# BuckRegulatorOnSer.net
KiCad netlist of a schematic drawn in Altium Designer
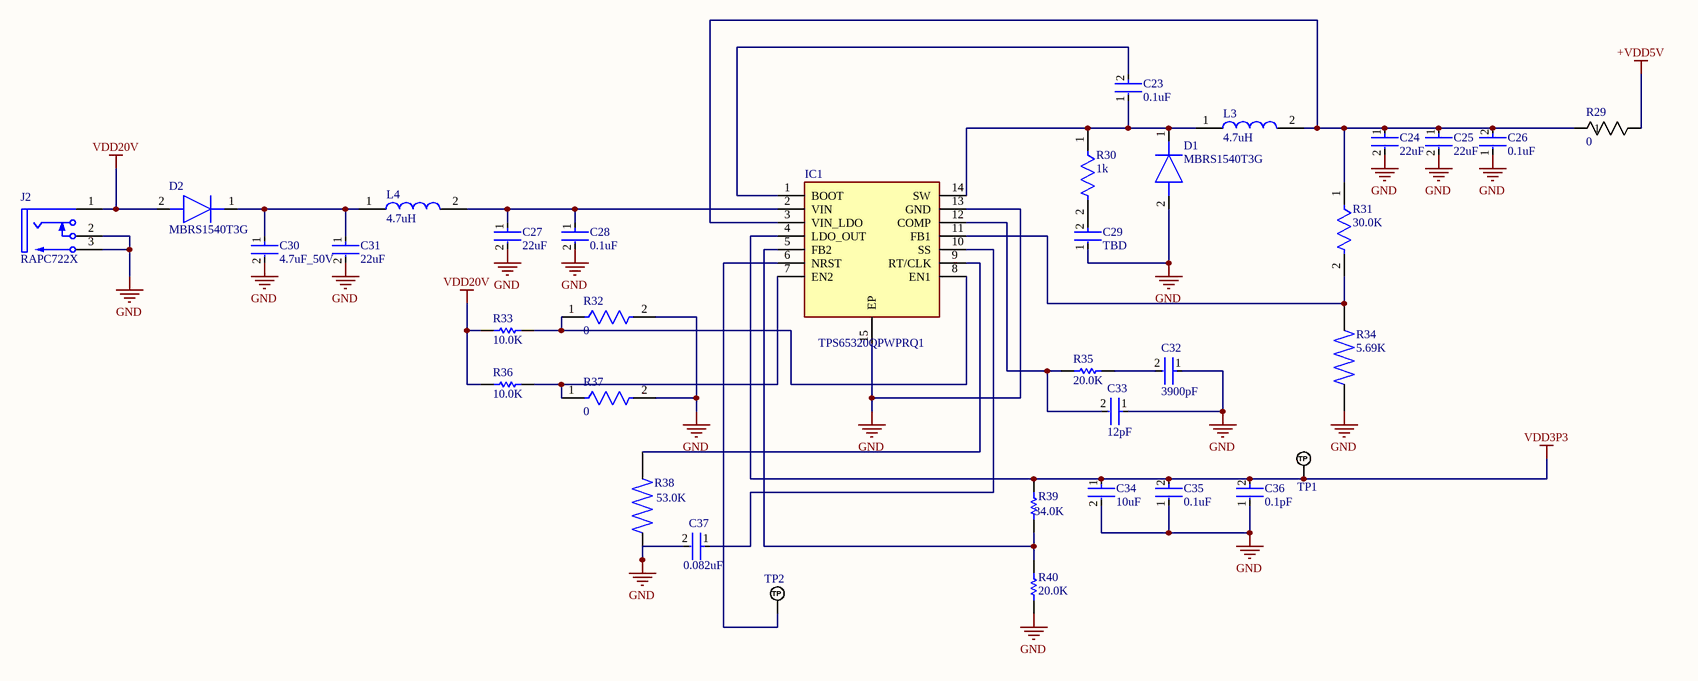
[diagram p0: BuckRegulatorOnSer.SchDoc]

(export (version "E")
  (design (tool "Eeschema 10.0.6"))
  (components
    (comp (ref "C23")
      (value "0.1uF")
      (footprint "FP-GRM15-MFG")
      (description "CAP CER 0.1UF 16V X7R 0402")
      (fields (field (name "MANUFACTURER PART NUMBER") "GRM155R71C104KA88D") (field (name "TOLERANCE") "10%"))
      (libsource (lib "Altium Content Vault") (part "236180d848d6139a670b325ea6854c9"))
    )
    (comp (ref "C24")
      (value "22uF")
      (footprint "FP-C3216-160-0_2-IPC_B")
      (description "Multilayer Ceramic Capacitors 22uF ±20% 25V X5R SMD 1206")
      (fields (field (name "TOLERANCE") "20%"))
      (libsource (lib "Altium Content Vault") (part "11868f565c42a9108669ba33697ecf6"))
    )
    (comp (ref "C25")
      (value "22uF")
      (footprint "FP-C3216-160-0_2-IPC_B")
      (description "Multilayer Ceramic Capacitors 22uF ±20% 25V X5R SMD 1206")
      (fields (field (name "TOLERANCE") "20%"))
      (libsource (lib "Altium Content Vault") (part "11868f565c42a9108669ba33697ecf6"))
    )
    (comp (ref "C26")
      (value "0.1uF")
      (footprint "FP-GRM15-MFG")
      (description "CAP CER 0.1UF 16V X7R 0402")
      (fields (field (name "MANUFACTURER PART NUMBER") "GRM155R71C104KA88D") (field (name "TOLERANCE") "10%"))
      (libsource (lib "Altium Content Vault") (part "236180d848d6139a670b325ea6854c9"))
    )
    (comp (ref "C27")
      (value "22uF")
      (footprint "FP-C3216-160-0_2-IPC_B")
      (description "Multilayer Ceramic Capacitors 22uF ±20% 25V X5R SMD 1206")
      (fields (field (name "TOLERANCE") "20%"))
      (libsource (lib "Altium Content Vault") (part "11868f565c42a9108669ba33697ecf6"))
    )
    (comp (ref "C28")
      (value "0.1uF")
      (footprint "FP-GRM188-0_1-e0_2_0_5-IPC_B")
      (description "Chip Multilayer Ceramic Capacitors for General Purpose, 0603, 0.10uF, X7R, 15%, 10%, 100V")
      (fields (field (name "VOLTAGE") "100V") (field (name "TOLERANCE") "10%"))
      (libsource (lib "Altium Content Vault") (part "11868f565c42a9108669ba33697ecf6"))
    )
    (comp (ref "C29")
      (value "TBD")
      (footprint "FP-GRM15-MFG")
      (description "CAP CER 0.1UF 16V X7R 0402")
      (fields (field (name "MANUFACTURER PART NUMBER") "GRM155R71C104KA88D") (field (name "TOLERANCE") "10%"))
      (libsource (lib "Altium Content Vault") (part "236180d848d6139a670b325ea6854c9"))
    )
    (comp (ref "C30")
      (value "4.7uF_50V")
      (footprint "FP-C3216-160-0_2-IPC_B")
      (description "Multilayer Ceramic Capacitors 4.7uF ±20% 50V X7R SMD 1206")
      (fields (field (name "TOLERANCE") "20%"))
      (libsource (lib "Altium Content Vault") (part "11868f565c42a9108669ba33697ecf6"))
    )
    (comp (ref "C31")
      (value "22uF")
      (footprint "FP-C3216-160-0_2-IPC_B")
      (description "Multilayer Ceramic Capacitors 22uF ±20% 25V X5R SMD 1206")
      (fields (field (name "TOLERANCE") "20%"))
      (libsource (lib "Altium Content Vault") (part "11868f565c42a9108669ba33697ecf6"))
    )
    (comp (ref "C32")
      (value "3900pF")
      (footprint "FP-C0402-BB-MFG")
      (description "CAP CER 3900PF 16V X7R 0402")
      (fields
        (field (name "MANUFACTURER PART NUMBER") "C0402C392K4RACTU")
        (field (name "OCTOPART") "https://octopart.com/c0402c392k4ractu-kemet-12577363")
      )
      (libsource (lib "Altium Content Vault") (part "b4654b650e69147ec39a6b967a45e02"))
    )
    (comp (ref "C33")
      (value "12pF")
      (footprint "FP-C0402-BB-MFG")
      (description "CAP CER 12PF 25V C0G/NP0 0402")
      (fields
        (field (name "OCTOPART") "https://octopart.com/c0402c120j3gacauto-kemet-21768529")
        (field (name "MANUFACTURER PART NUMBER") "C0402C120J3GACAUTO")
      )
      (libsource (lib "Altium Content Vault") (part "b4654b650e69147ec39a6b967a45e02"))
    )
    (comp (ref "C34")
      (value "10uF")
      (footprint "FP-C2012-125-0_2-MFG")
      (description "Multilayer Ceramic Capacitors 10μF ±10% 10V X7R SMD 0805")
      (fields (field (name "TOLERANCE") "10%") (field (name "VOLTAGE") "10V"))
      (libsource (lib "Altium Content Vault") (part "b4654b650e69147ec39a6b967a45e02"))
    )
    (comp (ref "C35")
      (value "0.1uF")
      (footprint "FP-GRM15-MFG")
      (description "CAP CER 0.1UF 16V X7R 0402")
      (fields (field (name "MANUFACTURER PART NUMBER") "GRM155R71C104KA88D") (field (name "TOLERANCE") "10%"))
      (libsource (lib "Altium Content Vault") (part "236180d848d6139a670b325ea6854c9"))
    )
    (comp (ref "C36")
      (value "0.1pF")
      (footprint "FP-GRM15-MFG")
      (description "CAP CER 0.1UF 16V X7R 0402")
      (fields (field (name "MANUFACTURER PART NUMBER") "GRM155R71C104KA88D") (field (name "TOLERANCE") "10%"))
      (libsource (lib "Altium Content Vault") (part "236180d848d6139a670b325ea6854c9"))
    )
    (comp (ref "C37")
      (value "0.082uF")
      (footprint "FP-C0402-BB-MFG")
      (fields
        (field (name "OCTOPART") "https://octopart.com/c0402c823k4ractu-kemet-134782")
        (field (name "MANUFACTURER") "Kemet")
        (field (name "TOLERANCE") "0.1")
      )
      (libsource (lib "Altium Content Vault") (part "b4654b650e69147ec39a6b967a45e02"))
    )
    (comp (ref "D1")
      (value "MBRS1540T3G")
      (footprint "SerDes_Eval_Board_Footprints:DIOM5436X256N")
      (description "Diode")
      (fields (field (name "MOUSER PART NUMBER") "863-MBRS1540T3G"))
      (libsource (lib "SerDes_Eval") (part "MBRS1540T3G"))
    )
    (comp (ref "D2")
      (value "MBRS1540T3G")
      (footprint "SerDes_Eval_Board_Footprints:DIOM5436X256N")
      (description "Diode")
      (fields (field (name "MOUSER PART NUMBER") "863-MBRS1540T3G"))
      (libsource (lib "SerDes_Eval") (part "MBRS1540T3G"))
    )
    (comp (ref "IC1")
      (value "TPS65320QPWPRQ1")
      (footprint "SerDes_Eval_Board_Footprints:SOP65P640X120-15N")
      (description "Integrated Circuit")
      (fields (field (name "MOUSER PART NUMBER") "595-TPS65320QPWPRQ1"))
      (libsource (lib "SerDes_Eval") (part "TPS65320QPWPRQ1"))
    )
    (comp (ref "J2")
      (value "RAPC722X")
      (footprint "SWITCH-RAPC712X-3_V")
      (description "Power Jack, 5 A, 3-Pin THD, RoHS, Bulk")
      (fields (field (name "MANUFACTURER") "Switchcraft"))
      (libsource (lib "Altium Content Vault") (part "SWITCH-RAPC712X-3"))
    )
    (comp (ref "L3")
      (value "4.7uH")
      (footprint "SerDes_Eval_Board_Footprints:XFL4020472MEB")
      (description "Inductor")
      (fields
        (field (name "MANUFACTURER_PART_NUMBER") "XFL4020-472MEB")
        (field (name "MOUSER PART NUMBER") "994-XFL4020-472MEB")
      )
      (libsource (lib "SerDes_Eval") (part "XFL4020-472MEB"))
    )
    (comp (ref "L4")
      (value "4.7uH")
      (footprint "SerDes_Eval_Board_Footprints:XFL4020472MEB")
      (description "Inductor")
      (fields
        (field (name "MANUFACTURER_PART_NUMBER") "XFL4020-472MEB")
        (field (name "MOUSER PART NUMBER") "994-XFL4020-472MEB")
      )
      (libsource (lib "SerDes_Eval") (part "XFL4020-472MEB"))
    )
    (comp (ref "R29")
      (value "0")
      (footprint "RC2512N_VIS")
      (description "CRCW2512-HP 0R0 E67 E3")
      (fields
        (field (name "MANUFACTURER_PART_NUMBER") "CRCW25120000Z0EGHP")
        (field (name "COPYRIGHT") "Copyright (C) 2025 Ultra Librarian. All rights reserved.")
      )
      (libsource (lib "CRCW25120000Z0EGHP") (part "CRCW25120000Z0EGHP"))
    )
    (comp (ref "R30")
      (value "1k")
      (footprint "FP-CRCW0603-e3-MFG")
      (description "RES Thick Film, 1kΩ, 1%, 0.1W, 100ppm/°C, 0603")
      (fields (field (name "TOLERANCE") "1%"))
      (libsource (lib "Altium Content Vault") (part "1029c3af85768c4190bb7ad29bc67b5"))
    )
    (comp (ref "R31")
      (value "30.0K")
      (footprint "FP-ERJ3EK-IPC_A")
      (description "RES SMD 30K OHM 1% 1/10W 0603")
      (fields (field (name "TOLERANCE") "1%"))
      (libsource (lib "Altium Content Vault") (part "1029c3af85768c4190bb7ad29bc67b5"))
    )
    (comp (ref "R32")
      (value "0")
      (footprint "FP-ERJ-3GEY0R00V-MFG")
      (description "RES SMD 0 OHM JUMPER 1/10W 0603")
      (fields (field (name "TOLERANCE") "5%") (field (name "MANUFACTURER PART NUMBER") "ERJ-3GEY0R00V"))
      (libsource (lib "Altium Content Vault") (part "1029c3af85768c4190bb7ad29bc67b5"))
    )
    (comp (ref "R33")
      (value "10.0K")
      (footprint "RESC1609X55X30LL15T15")
      (description "Chip Resistor, 10 KOhm, +/- 1%, 0.1 W, -55 to 155 degC, 0603 (1608 Metric), RoHS, Tape and Reel")
      (fields (field (name "TOLERANCE") "1%") (field (name "MANUFACTURER") "Panasonic"))
      (libsource (lib "Altium Content Vault") (part "RES-2"))
    )
    (comp (ref "R34")
      (value "5.69K")
      (footprint "RESC1608X46N:RESC1608X46N")
      (fields (field (name "MP") "PAT0603E5691BST1"))
      (libsource (lib "PAT0603E5691BST1") (part "PAT0603E5691BST1"))
    )
    (comp (ref "R35")
      (value "20.0K")
      (footprint "RESC1608X55X30ML15T15")
      (fields (field (name "PART NUMBER") "ERJ-3EKF2002V") (field (name "MANUFACTURER") "Panasonic"))
      (libsource (lib "Altium Content Vault") (part "RES"))
    )
    (comp (ref "R36")
      (value "10.0K")
      (footprint "RESC1609X55X30LL15T15")
      (description "Chip Resistor, 10 KOhm, +/- 1%, 0.1 W, -55 to 155 degC, 0603 (1608 Metric), RoHS, Tape and Reel")
      (fields (field (name "TOLERANCE") "1%") (field (name "MANUFACTURER") "Panasonic"))
      (libsource (lib "Altium Content Vault") (part "RES-2"))
    )
    (comp (ref "R37")
      (value "0")
      (footprint "FP-ERJ-3GEY0R00V-MFG")
      (description "RES SMD 0 OHM JUMPER 1/10W 0603")
      (fields (field (name "TOLERANCE") "5%") (field (name "MANUFACTURER PART NUMBER") "ERJ-3GEY0R00V"))
      (libsource (lib "Altium Content Vault") (part "1029c3af85768c4190bb7ad29bc67b5"))
    )
    (comp (ref "R38")
      (value "53.0K")
      (footprint "RESC1608X46N")
      (fields (field (name "MP") "PAT0603E5302BST1"))
      (libsource (lib "PAT0603E5302BST1") (part "PAT0603E5302BST1"))
    )
    (comp (ref "R39")
      (value "34.0K")
      (footprint "RESC1608X55X30ML15T15")
      (fields (field (name "PART NUMBER") "ERJ-3EKF3402V") (field (name "MANUFACTURER") "Panasonic"))
      (libsource (lib "Altium Content Vault") (part "RES"))
    )
    (comp (ref "R40")
      (value "20.0K")
      (footprint "RESC1608X55X30ML15T15")
      (fields (field (name "PART NUMBER") "ERJ-3EKF2002V") (field (name "MANUFACTURER") "Panasonic"))
      (libsource (lib "Altium Content Vault") (part "RES"))
    )
    (comp (ref "TP1")
      (value "TP_NOBOM")
      (footprint "PAD_RND_1MM")
      (description "Test Point Round 1mm (NO BOM)")
      (libsource (lib "Custom_Schematic-Lib") (part "TEST_POINT_RND_1MM"))
    )
    (comp (ref "TP2")
      (value "TP_NOBOM")
      (footprint "PAD_RND_1MM")
      (description "Test Point Round 1mm (NO BOM)")
      (libsource (lib "Custom_Schematic-Lib") (part "TEST_POINT_RND_1MM"))
    )
  )
  (nets
    (net (code "1") (name "+VDD5V") (class "Default")
      (node (ref "R29") (pin "2") (pinfunction "2_2") (pintype "passive"))
    )
    (net (code "2") (name "GND") (class "Default")
      (node (ref "C24") (pin "2") (pinfunction "2_2") (pintype "passive"))
      (node (ref "C25") (pin "2") (pinfunction "2_2") (pintype "passive"))
      (node (ref "C26") (pin "1") (pinfunction "1_1") (pintype "passive"))
      (node (ref "C27") (pin "2") (pinfunction "2_2") (pintype "passive"))
      (node (ref "C28") (pin "2") (pinfunction "2_2") (pintype "passive"))
      (node (ref "C29") (pin "1") (pinfunction "1_1") (pintype "passive"))
      (node (ref "C30") (pin "2") (pinfunction "2_2") (pintype "passive"))
      (node (ref "C31") (pin "2") (pinfunction "2_2") (pintype "passive"))
      (node (ref "C32") (pin "1") (pinfunction "1_1") (pintype "passive"))
      (node (ref "C33") (pin "1") (pinfunction "1_1") (pintype "passive"))
      (node (ref "C34") (pin "2") (pinfunction "2_2") (pintype "passive"))
      (node (ref "C35") (pin "1") (pinfunction "1_1") (pintype "passive"))
      (node (ref "C36") (pin "1") (pinfunction "1_1") (pintype "passive"))
      (node (ref "C37") (pin "2") (pinfunction "2_2") (pintype "passive"))
      (node (ref "D1") (pin "2") (pinfunction "A_2") (pintype "passive"))
      (node (ref "IC1") (pin "13") (pinfunction "GND_13") (pintype "passive"))
      (node (ref "IC1") (pin "15") (pinfunction "EP_15") (pintype "passive"))
      (node (ref "J2") (pin "2") (pinfunction "2_2") (pintype "passive"))
      (node (ref "J2") (pin "3") (pinfunction "3_3") (pintype "passive"))
      (node (ref "R32") (pin "2") (pinfunction "2_2") (pintype "passive"))
      (node (ref "R34") (pin "2") (pinfunction "2_2") (pintype "passive"))
      (node (ref "R37") (pin "2") (pinfunction "2_2") (pintype "passive"))
      (node (ref "R38") (pin "2") (pinfunction "2_2") (pintype "passive"))
      (node (ref "R40") (pin "2") (pinfunction "2_2") (pintype "passive"))
    )
    (net (code "3") (name "Net-(C29-Pad2)") (class "Default")
      (node (ref "C29") (pin "2") (pinfunction "2_2") (pintype "passive"))
      (node (ref "R30") (pin "2") (pinfunction "2_2") (pintype "passive"))
    )
    (net (code "4") (name "Net-(C32-Pad2)") (class "Default")
      (node (ref "C32") (pin "2") (pinfunction "2_2") (pintype "passive"))
      (node (ref "R35") (pin "2") (pinfunction "2_2") (pintype "passive"))
    )
    (net (code "5") (name "Net-(D1-K)") (class "Default")
      (node (ref "C23") (pin "1") (pinfunction "1_1") (pintype "passive"))
      (node (ref "D1") (pin "1") (pinfunction "K_1") (pintype "passive"))
      (node (ref "IC1") (pin "14") (pinfunction "SW_14") (pintype "passive"))
      (node (ref "L3") (pin "1") (pinfunction "1_1") (pintype "passive"))
      (node (ref "R30") (pin "1") (pinfunction "1_1") (pintype "passive"))
    )
    (net (code "6") (name "Net-(D2-K)") (class "Default")
      (node (ref "C30") (pin "1") (pinfunction "1_1") (pintype "passive"))
      (node (ref "C31") (pin "1") (pinfunction "1_1") (pintype "passive"))
      (node (ref "D2") (pin "1") (pinfunction "K_1") (pintype "passive"))
      (node (ref "L4") (pin "1") (pinfunction "1_1") (pintype "passive"))
    )
    (net (code "7") (name "Net-(IC1-BOOT)") (class "Default")
      (node (ref "C23") (pin "2") (pinfunction "2_2") (pintype "passive"))
      (node (ref "IC1") (pin "1") (pinfunction "BOOT_1") (pintype "passive"))
    )
    (net (code "8") (name "Net-(IC1-COMP)") (class "Default")
      (node (ref "C33") (pin "2") (pinfunction "2_2") (pintype "passive"))
      (node (ref "IC1") (pin "12") (pinfunction "COMP_12") (pintype "passive"))
      (node (ref "R35") (pin "1") (pinfunction "1_1") (pintype "passive"))
    )
    (net (code "9") (name "Net-(IC1-EN1)") (class "Default")
      (node (ref "IC1") (pin "8") (pinfunction "EN1_8") (pintype "passive"))
      (node (ref "R32") (pin "1") (pinfunction "1_1") (pintype "passive"))
      (node (ref "R33") (pin "2") (pinfunction "2_2") (pintype "passive"))
    )
    (net (code "10") (name "Net-(IC1-EN2)") (class "Default")
      (node (ref "IC1") (pin "7") (pinfunction "EN2_7") (pintype "passive"))
      (node (ref "R36") (pin "2") (pinfunction "2_2") (pintype "passive"))
      (node (ref "R37") (pin "1") (pinfunction "1_1") (pintype "passive"))
    )
    (net (code "11") (name "Net-(IC1-FB1)") (class "Default")
      (node (ref "IC1") (pin "11") (pinfunction "FB1_11") (pintype "passive"))
      (node (ref "R31") (pin "2") (pinfunction "2_2") (pintype "passive"))
      (node (ref "R34") (pin "1") (pinfunction "1_1") (pintype "passive"))
    )
    (net (code "12") (name "Net-(IC1-FB2)") (class "Default")
      (node (ref "IC1") (pin "5") (pinfunction "FB2_5") (pintype "passive"))
      (node (ref "R39") (pin "2") (pinfunction "2_2") (pintype "passive"))
      (node (ref "R40") (pin "1") (pinfunction "1_1") (pintype "passive"))
    )
    (net (code "13") (name "Net-(IC1-NRST)") (class "Default")
      (node (ref "IC1") (pin "6") (pinfunction "NRST_6") (pintype "passive"))
      (node (ref "TP2") (pin "1") (pinfunction "TP_1") (pintype "passive"))
    )
    (net (code "14") (name "Net-(IC1-RT{slash}CLK)") (class "Default")
      (node (ref "IC1") (pin "9") (pinfunction "RT/CLK_9") (pintype "passive"))
      (node (ref "R38") (pin "1") (pinfunction "1_1") (pintype "passive"))
    )
    (net (code "15") (name "Net-(IC1-SS)") (class "Default")
      (node (ref "C37") (pin "1") (pinfunction "1_1") (pintype "passive"))
      (node (ref "IC1") (pin "10") (pinfunction "SS_10") (pintype "passive"))
    )
    (net (code "16") (name "Net-(IC1-VIN)") (class "Default")
      (node (ref "C27") (pin "1") (pinfunction "1_1") (pintype "passive"))
      (node (ref "C28") (pin "1") (pinfunction "1_1") (pintype "passive"))
      (node (ref "IC1") (pin "2") (pinfunction "VIN_2") (pintype "passive"))
      (node (ref "L4") (pin "2") (pinfunction "2_2") (pintype "passive"))
    )
    (net (code "17") (name "Net-(IC1-VIN_LDO)") (class "Default")
      (node (ref "C24") (pin "1") (pinfunction "1_1") (pintype "passive"))
      (node (ref "C25") (pin "1") (pinfunction "1_1") (pintype "passive"))
      (node (ref "C26") (pin "2") (pinfunction "2_2") (pintype "passive"))
      (node (ref "IC1") (pin "3") (pinfunction "VIN_LDO_3") (pintype "passive"))
      (node (ref "L3") (pin "2") (pinfunction "2_2") (pintype "passive"))
      (node (ref "R29") (pin "1") (pinfunction "1_1") (pintype "passive"))
      (node (ref "R31") (pin "1") (pinfunction "1_1") (pintype "passive"))
    )
    (net (code "18") (name "VDD3P3") (class "Default")
      (node (ref "C34") (pin "1") (pinfunction "1_1") (pintype "passive"))
      (node (ref "C35") (pin "2") (pinfunction "2_2") (pintype "passive"))
      (node (ref "C36") (pin "2") (pinfunction "2_2") (pintype "passive"))
      (node (ref "IC1") (pin "4") (pinfunction "LDO_OUT_4") (pintype "passive"))
      (node (ref "R39") (pin "1") (pinfunction "1_1") (pintype "passive"))
      (node (ref "TP1") (pin "1") (pinfunction "TP_1") (pintype "passive"))
    )
    (net (code "19") (name "VDD20V") (class "Default")
      (node (ref "D2") (pin "2") (pinfunction "A_2") (pintype "passive"))
      (node (ref "J2") (pin "1") (pinfunction "1_1") (pintype "passive"))
      (node (ref "R33") (pin "1") (pinfunction "1_1") (pintype "passive"))
      (node (ref "R36") (pin "1") (pinfunction "1_1") (pintype "passive"))
    )
  )
)
